# Board.net
KiCad netlist of a schematic drawn in EAGLE
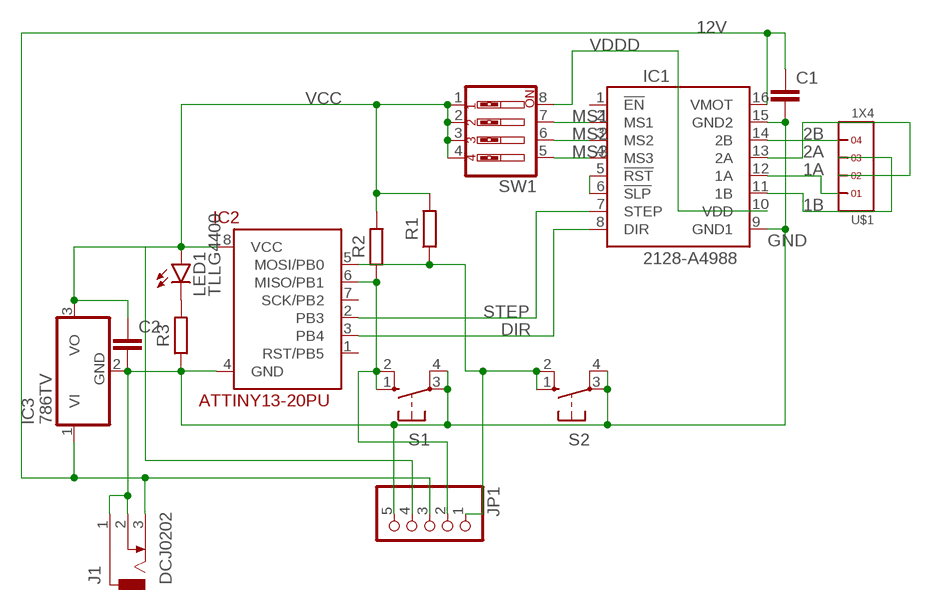
[diagram p0: schematic, sheet 1]

(export (version "E")
  (design (tool "Eeschema 10.0.6"))
  (components
    (comp (ref "C1")
      (value "C2.5/6")
      (footprint "eagle-import:C2.5-6")
      (libsource (lib "eagle-import") (part "C2.5/6"))
    )
    (comp (ref "C2")
      (value "C2.5/6")
      (footprint "eagle-import:C2.5-6")
      (libsource (lib "eagle-import") (part "C2.5/6"))
    )
    (comp (ref "IC1")
      (value "2128-A4988")
      (footprint "eagle-import:A4988")
      (libsource (lib "eagle-import") (part "2128-A4988"))
    )
    (comp (ref "IC2")
      (value "ATTINY13-20PU")
      (footprint "eagle-import:DIL08")
      (libsource (lib "eagle-import") (part "ATTINY13-20PU"))
    )
    (comp (ref "IC3")
      (value "786TV")
      (footprint "eagle-import:TO220V")
      (libsource (lib "eagle-import") (part "78TV6"))
    )
    (comp (ref "J1")
      (value "DCJ0202")
      (footprint "eagle-import:DCJ0202")
      (libsource (lib "eagle-import") (part "DCJ0202"))
    )
    (comp (ref "JP1")
      (value "PINHD-1X5")
      (footprint "eagle-import:1X05")
      (libsource (lib "eagle-import") (part "PINHD-1X5"))
    )
    (comp (ref "LED1")
      (value "TLLG4400")
      (footprint "eagle-import:LED3MM")
      (fields (field (name "MF") "VISHAY SEMICONDUCTOR"))
      (libsource (lib "eagle-import") (part "TLLG4400"))
    )
    (comp (ref "R1")
      (value "R_AXIAL-7.2MM-PITCH")
      (footprint "eagle-import:RESAD724W46L381D178B")
      (libsource (lib "eagle-import") (part "RAXIAL-7.2MM-PITCH_"))
    )
    (comp (ref "R2")
      (value "R_AXIAL-7.2MM-PITCH")
      (footprint "eagle-import:RESAD724W46L381D178B")
      (libsource (lib "eagle-import") (part "RAXIAL-7.2MM-PITCH_"))
    )
    (comp (ref "R3")
      (value "R_AXIAL-7.2MM-PITCH")
      (footprint "eagle-import:RESAD724W46L381D178B")
      (libsource (lib "eagle-import") (part "RAXIAL-7.2MM-PITCH_"))
    )
    (comp (ref "S1")
      (value "10-XX")
      (footprint "eagle-import:B3F-10XX")
      (fields (field (name "MPN") "B3F-1000"))
      (libsource (lib "eagle-import") (part "10-XX"))
    )
    (comp (ref "S2")
      (value "10-XX")
      (footprint "eagle-import:B3F-10XX")
      (fields (field (name "MPN") "B3F-1000"))
      (libsource (lib "eagle-import") (part "10-XX"))
    )
    (comp (ref "SW1")
      (value "SW_DIP-4")
      (footprint "eagle-import:EDG-04")
      (libsource (lib "eagle-import") (part "SW_DIP-4"))
    )
    (comp (ref "U$1")
      (value "1X4")
      (footprint "eagle-import:1X4")
      (libsource (lib "eagle-import") (part "1X4"))
    )
  )
  (nets
    (net (code "1") (name "/1A") (class "Default")
      (node (ref "IC1") (pin "12") (pinfunction "1A_12") (pintype "output"))
      (node (ref "U$1") (pin "1") (pinfunction "1_1") (pintype "bidirectional"))
    )
    (net (code "2") (name "/1B") (class "Default")
      (node (ref "IC1") (pin "11") (pinfunction "1B_11") (pintype "output"))
      (node (ref "U$1") (pin "3") (pinfunction "3_3") (pintype "bidirectional"))
    )
    (net (code "3") (name "/2A") (class "Default")
      (node (ref "IC1") (pin "13") (pinfunction "2A_13") (pintype "output"))
      (node (ref "U$1") (pin "2") (pinfunction "2_2") (pintype "bidirectional"))
    )
    (net (code "4") (name "/2B") (class "Default")
      (node (ref "IC1") (pin "14") (pinfunction "2B_14") (pintype "output"))
      (node (ref "U$1") (pin "4") (pinfunction "4_4") (pintype "bidirectional"))
    )
    (net (code "5") (name "/12V") (class "Default")
      (node (ref "C1") (pin "1") (pinfunction "1_1") (pintype "passive"))
      (node (ref "IC1") (pin "16") (pinfunction "VMOT_16") (pintype "power_in"))
      (node (ref "IC3") (pin "1") (pinfunction "VI_1") (pintype "input"))
      (node (ref "J1") (pin "3") (pinfunction "3_3") (pintype "passive"))
      (node (ref "JP1") (pin "3") (pinfunction "3_3") (pintype "passive"))
    )
    (net (code "6") (name "/DIR") (class "Default")
      (node (ref "IC1") (pin "8") (pinfunction "DIR_8") (pintype "input"))
      (node (ref "IC2") (pin "3") (pinfunction "PB4_3") (pintype "bidirectional"))
    )
    (net (code "7") (name "/GND") (class "Default")
      (node (ref "C1") (pin "2") (pinfunction "2_2") (pintype "passive"))
      (node (ref "C2") (pin "2") (pinfunction "2_2") (pintype "passive"))
      (node (ref "IC1") (pin "15") (pinfunction "GND2_15") (pintype "power_in"))
      (node (ref "IC1") (pin "9") (pinfunction "GND1_9") (pintype "power_in"))
      (node (ref "IC2") (pin "4") (pinfunction "GND_4") (pintype "power_in"))
      (node (ref "IC3") (pin "2") (pinfunction "GND_2") (pintype "passive"))
      (node (ref "J1") (pin "1") (pinfunction "1_1") (pintype "passive"))
      (node (ref "J1") (pin "2") (pinfunction "2_2") (pintype "passive"))
      (node (ref "JP1") (pin "5") (pinfunction "5_5") (pintype "passive"))
      (node (ref "R3") (pin "1") (pinfunction "1_1") (pintype "passive"))
      (node (ref "S1") (pin "3") (pinfunction "P_3") (pintype "passive"))
      (node (ref "S1") (pin "4") (pinfunction "P1_4") (pintype "passive"))
      (node (ref "S2") (pin "3") (pinfunction "P_3") (pintype "passive"))
      (node (ref "S2") (pin "4") (pinfunction "P1_4") (pintype "passive"))
    )
    (net (code "8") (name "/MS1") (class "Default")
      (node (ref "IC1") (pin "2") (pinfunction "MS1_2") (pintype "passive"))
      (node (ref "SW1") (pin "7") (pinfunction "7_7") (pintype "passive"))
    )
    (net (code "9") (name "/MS2") (class "Default")
      (node (ref "IC1") (pin "3") (pinfunction "MS2_3") (pintype "passive"))
      (node (ref "SW1") (pin "6") (pinfunction "6_6") (pintype "passive"))
    )
    (net (code "10") (name "/MS3") (class "Default")
      (node (ref "IC1") (pin "4") (pinfunction "MS3_4") (pintype "passive"))
      (node (ref "SW1") (pin "5") (pinfunction "5_5") (pintype "passive"))
    )
    (net (code "11") (name "/STEP") (class "Default")
      (node (ref "IC1") (pin "7") (pinfunction "STEP_7") (pintype "input"))
      (node (ref "IC2") (pin "2") (pinfunction "PB3_2") (pintype "bidirectional"))
    )
    (net (code "12") (name "/VCC") (class "Default")
      (node (ref "C2") (pin "1") (pinfunction "1_1") (pintype "passive"))
      (node (ref "IC2") (pin "8") (pinfunction "VCC_8") (pintype "power_in"))
      (node (ref "IC3") (pin "3") (pinfunction "VO_3") (pintype "passive"))
      (node (ref "JP1") (pin "4") (pinfunction "4_4") (pintype "passive"))
      (node (ref "LED1") (pin "A") (pinfunction "A_A") (pintype "passive"))
      (node (ref "R1") (pin "2") (pinfunction "2_2") (pintype "passive"))
      (node (ref "R2") (pin "2") (pinfunction "2_2") (pintype "passive"))
      (node (ref "SW1") (pin "1") (pinfunction "1_1") (pintype "passive"))
      (node (ref "SW1") (pin "2") (pinfunction "2_2") (pintype "passive"))
      (node (ref "SW1") (pin "3") (pinfunction "3_3") (pintype "passive"))
      (node (ref "SW1") (pin "4") (pinfunction "4_4") (pintype "passive"))
    )
    (net (code "13") (name "/VDDD") (class "Default")
      (node (ref "IC1") (pin "10") (pinfunction "VDD_10") (pintype "power_in"))
      (node (ref "SW1") (pin "8") (pinfunction "8_8") (pintype "passive"))
    )
    (net (code "14") (name "Net-(IC1-~{RST})") (class "Default")
      (node (ref "IC1") (pin "5") (pinfunction "~{RST}_5") (pintype "passive"))
      (node (ref "IC1") (pin "6") (pinfunction "~{SLP}_6") (pintype "passive"))
    )
    (net (code "15") (name "Net-(IC2-MISO{slash}PB1)") (class "Default")
      (node (ref "IC2") (pin "6") (pinfunction "MISO/PB1_6") (pintype "bidirectional"))
      (node (ref "JP1") (pin "2") (pinfunction "2_2") (pintype "passive"))
      (node (ref "R2") (pin "1") (pinfunction "1_1") (pintype "passive"))
      (node (ref "S1") (pin "1") (pinfunction "S_1") (pintype "passive"))
      (node (ref "S1") (pin "2") (pinfunction "S1_2") (pintype "passive"))
    )
    (net (code "16") (name "Net-(IC2-MOSI{slash}PB0)") (class "Default")
      (node (ref "IC2") (pin "5") (pinfunction "MOSI/PB0_5") (pintype "bidirectional"))
      (node (ref "JP1") (pin "1") (pinfunction "1_1") (pintype "passive"))
      (node (ref "R1") (pin "1") (pinfunction "1_1") (pintype "passive"))
      (node (ref "S2") (pin "1") (pinfunction "S_1") (pintype "passive"))
      (node (ref "S2") (pin "2") (pinfunction "S1_2") (pintype "passive"))
    )
    (net (code "17") (name "Net-(LED1-C)") (class "Default")
      (node (ref "LED1") (pin "K") (pinfunction "C_K") (pintype "passive"))
      (node (ref "R3") (pin "2") (pinfunction "2_2") (pintype "passive"))
    )
    (net (code "18") (name "unconnected-(IC1-~{EN}-Pad1)") (class "Default")
      (node (ref "IC1") (pin "1") (pinfunction "~{EN}_1") (pintype "passive"))
    )
    (net (code "19") (name "unconnected-(IC2-RST{slash}PB5-Pad1)") (class "Default")
      (node (ref "IC2") (pin "1") (pinfunction "RST/PB5_1") (pintype "bidirectional"))
    )
    (net (code "20") (name "unconnected-(IC2-SCK{slash}PB2-Pad7)") (class "Default")
      (node (ref "IC2") (pin "7") (pinfunction "SCK/PB2_7") (pintype "bidirectional"))
    )
  )
)
